# voltage_cond.net
KiCad netlist of a schematic drawn in Altium Designer
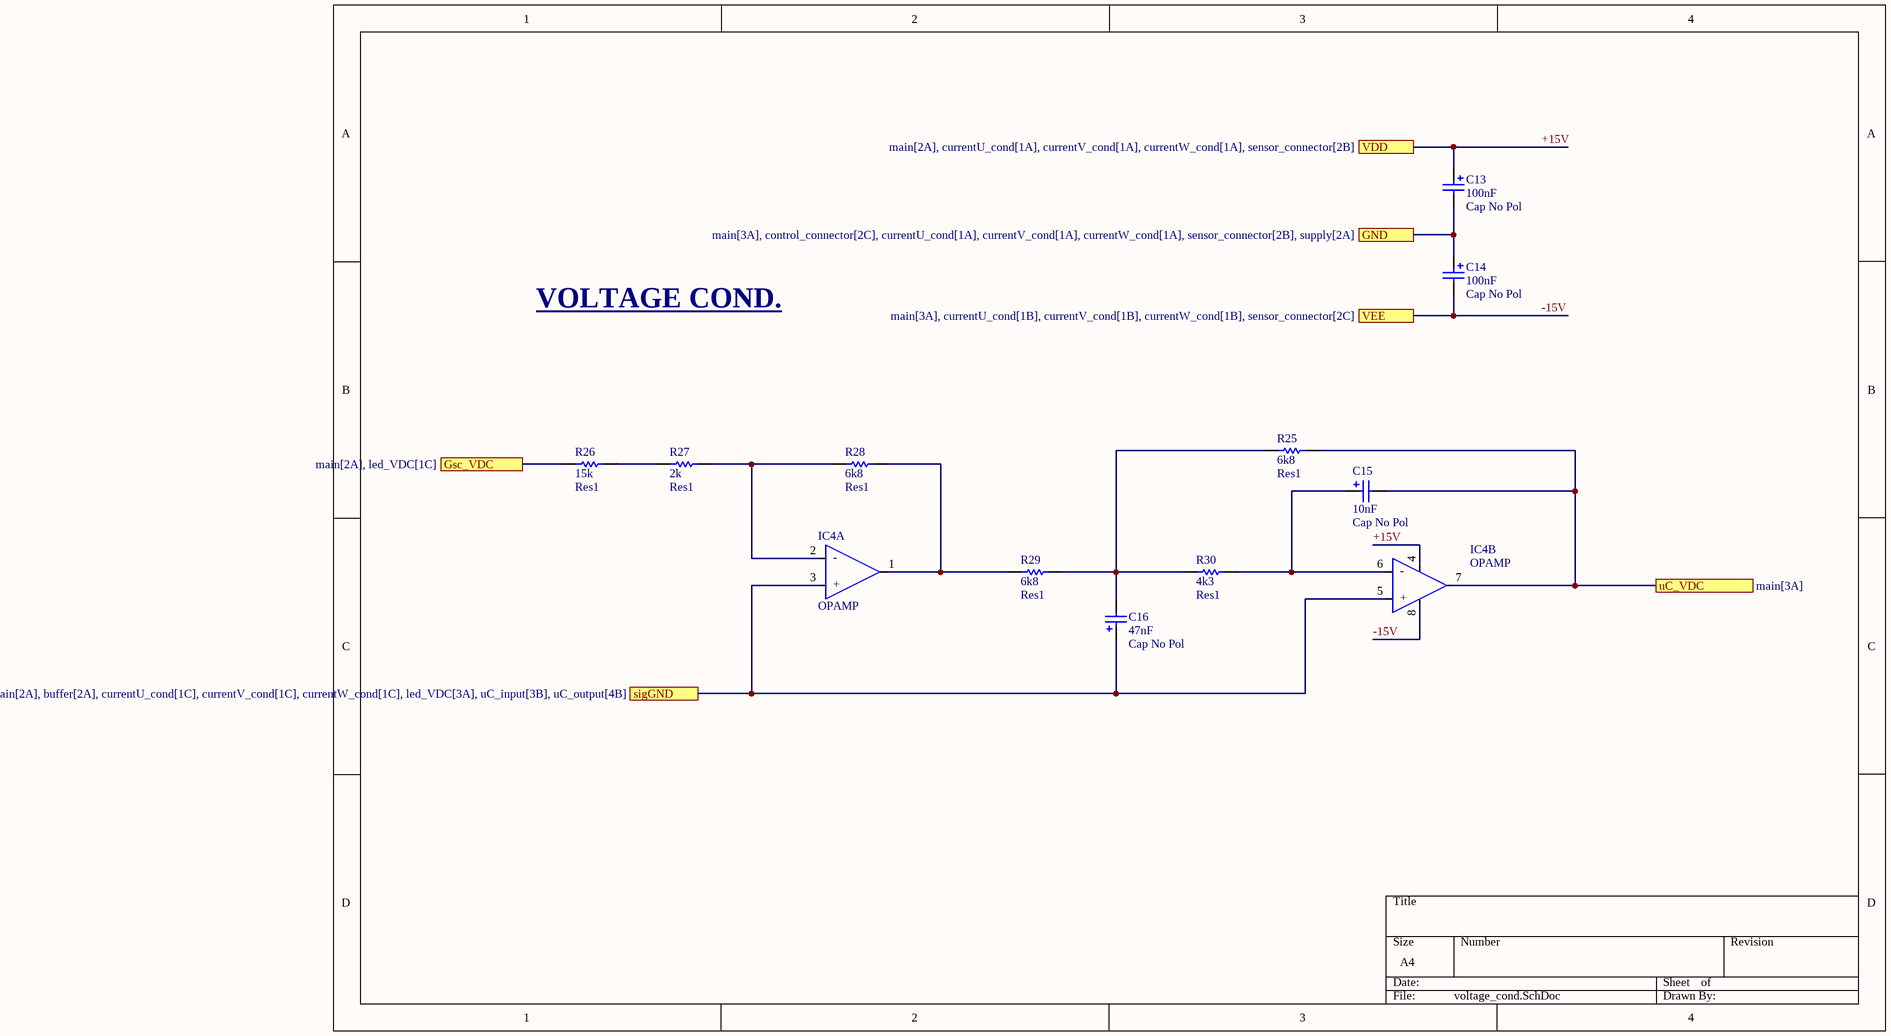
[diagram p0: voltage_cond.SchDoc]

(export (version "E")
  (design (tool "Eeschema 10.0.6"))
  (components
    (comp (ref "C13")
      (value "Cap No Pol")
      (footprint "RAD-0.1_mod")
      (description "Polarized Capacitor (Radial)")
      (fields (field (name "ALTIUM_VALUE") "100nF") (field (name "PUBLISHER") "Altium Limited"))
      (libsource (lib "LABSTEPS_Project") (part "Cap No Pol"))
    )
    (comp (ref "C14")
      (value "Cap No Pol")
      (footprint "RAD-0.1_mod")
      (description "Polarized Capacitor (Radial)")
      (fields (field (name "ALTIUM_VALUE") "100nF") (field (name "PUBLISHER") "Altium Limited"))
      (libsource (lib "LABSTEPS_Project") (part "Cap No Pol"))
    )
    (comp (ref "C15")
      (value "Cap No Pol")
      (footprint "RAD-0.1_mod")
      (description "Polarized Capacitor (Radial)")
      (fields (field (name "ALTIUM_VALUE") "10nF") (field (name "PUBLISHER") "Altium Limited"))
      (libsource (lib "LABSTEPS_Project") (part "Cap No Pol"))
    )
    (comp (ref "C16")
      (value "Cap No Pol")
      (footprint "RAD-0.1_mod")
      (description "Polarized Capacitor (Radial)")
      (fields (field (name "ALTIUM_VALUE") "47nF") (field (name "PUBLISHER") "Altium Limited"))
      (libsource (lib "LABSTEPS_Project") (part "Cap No Pol"))
    )
    (comp (ref "IC4")
      (value "OPAMP")
      (footprint "DIP-8_mod")
      (description "ADTL082")
      (libsource (lib "LABSTEPS_Project") (part "ADTL082"))
    )
    (comp (ref "R25")
      (value "Res1")
      (footprint "AXIAL-0.3_mod")
      (description "Resistor")
      (fields (field (name "ALTIUM_VALUE") "6k8") (field (name "PUBLISHER") "Altium Limited"))
      (libsource (lib "LABSTEPS_Project") (part "Res1"))
    )
    (comp (ref "R26")
      (value "Res1")
      (footprint "AXIAL-0.3_mod")
      (description "Resistor")
      (fields (field (name "ALTIUM_VALUE") "15k") (field (name "PUBLISHER") "Altium Limited"))
      (libsource (lib "LABSTEPS_Project") (part "Res1"))
    )
    (comp (ref "R27")
      (value "Res1")
      (footprint "AXIAL-0.3_mod")
      (description "Resistor")
      (fields (field (name "ALTIUM_VALUE") "2k") (field (name "PUBLISHER") "Altium Limited"))
      (libsource (lib "LABSTEPS_Project") (part "Res1"))
    )
    (comp (ref "R28")
      (value "Res1")
      (footprint "AXIAL-0.3_mod")
      (description "Resistor")
      (fields (field (name "ALTIUM_VALUE") "6k8") (field (name "PUBLISHER") "Altium Limited"))
      (libsource (lib "LABSTEPS_Project") (part "Res1"))
    )
    (comp (ref "R29")
      (value "Res1")
      (footprint "AXIAL-0.3_mod")
      (description "Resistor")
      (fields (field (name "ALTIUM_VALUE") "6k8") (field (name "PUBLISHER") "Altium Limited"))
      (libsource (lib "LABSTEPS_Project") (part "Res1"))
    )
    (comp (ref "R30")
      (value "Res1")
      (footprint "AXIAL-0.3_mod")
      (description "Resistor")
      (fields (field (name "ALTIUM_VALUE") "4k3") (field (name "PUBLISHER") "Altium Limited"))
      (libsource (lib "LABSTEPS_Project") (part "Res1"))
    )
  )
  (nets
    (net (code "1") (name "/+15V") (class "Default")
      (node (ref "C13") (pin "1") (pinfunction "1_1") (pintype "passive"))
      (node (ref "IC4") (pin "4") (pinfunction "-V_4") (pintype "passive"))
    )
    (net (code "2") (name "/-15V") (class "Default")
      (node (ref "C14") (pin "2") (pinfunction "2_2") (pintype "passive"))
      (node (ref "IC4") (pin "8") (pinfunction "V+_8") (pintype "passive"))
    )
    (net (code "3") (name "/GND") (class "Default")
      (node (ref "C13") (pin "2") (pinfunction "2_2") (pintype "passive"))
      (node (ref "C14") (pin "1") (pinfunction "1_1") (pintype "passive"))
    )
    (net (code "4") (name "/Gsc_VDC") (class "Default")
      (node (ref "R26") (pin "1") (pinfunction "1_1") (pintype "passive"))
    )
    (net (code "5") (name "/sigGND") (class "Default")
      (node (ref "C16") (pin "1") (pinfunction "1_1") (pintype "passive"))
      (node (ref "IC4") (pin "3") (pinfunction "IN_A_+_3") (pintype "passive"))
      (node (ref "IC4") (pin "5") (pinfunction "IN_B_+_5") (pintype "passive"))
    )
    (net (code "6") (name "/uC_VDC") (class "Default")
      (node (ref "C15") (pin "2") (pinfunction "2_2") (pintype "passive"))
      (node (ref "IC4") (pin "7") (pinfunction "OUT_B_7") (pintype "passive"))
      (node (ref "R25") (pin "2") (pinfunction "2_2") (pintype "passive"))
    )
    (net (code "7") (name "Net-(C16-Pad2)") (class "Default")
      (node (ref "C16") (pin "2") (pinfunction "2_2") (pintype "passive"))
      (node (ref "R25") (pin "1") (pinfunction "1_1") (pintype "passive"))
      (node (ref "R29") (pin "2") (pinfunction "2_2") (pintype "passive"))
      (node (ref "R30") (pin "1") (pinfunction "1_1") (pintype "passive"))
    )
    (net (code "8") (name "Net-(IC4A-IN_A_-)") (class "Default")
      (node (ref "IC4") (pin "2") (pinfunction "IN_A_-_2") (pintype "passive"))
      (node (ref "R27") (pin "2") (pinfunction "2_2") (pintype "passive"))
      (node (ref "R28") (pin "1") (pinfunction "1_1") (pintype "passive"))
    )
    (net (code "9") (name "Net-(IC4A-OUT_A)") (class "Default")
      (node (ref "IC4") (pin "1") (pinfunction "OUT_A_1") (pintype "passive"))
      (node (ref "R28") (pin "2") (pinfunction "2_2") (pintype "passive"))
      (node (ref "R29") (pin "1") (pinfunction "1_1") (pintype "passive"))
    )
    (net (code "10") (name "Net-(IC4B-IN_B_-)") (class "Default")
      (node (ref "C15") (pin "1") (pinfunction "1_1") (pintype "passive"))
      (node (ref "IC4") (pin "6") (pinfunction "IN_B_-_6") (pintype "passive"))
      (node (ref "R30") (pin "2") (pinfunction "2_2") (pintype "passive"))
    )
    (net (code "11") (name "Net-(R26-Pad2)") (class "Default")
      (node (ref "R26") (pin "2") (pinfunction "2_2") (pintype "passive"))
      (node (ref "R27") (pin "1") (pinfunction "1_1") (pintype "passive"))
    )
  )
)
